# MCU.net
KiCad netlist of a schematic drawn in Altium Designer
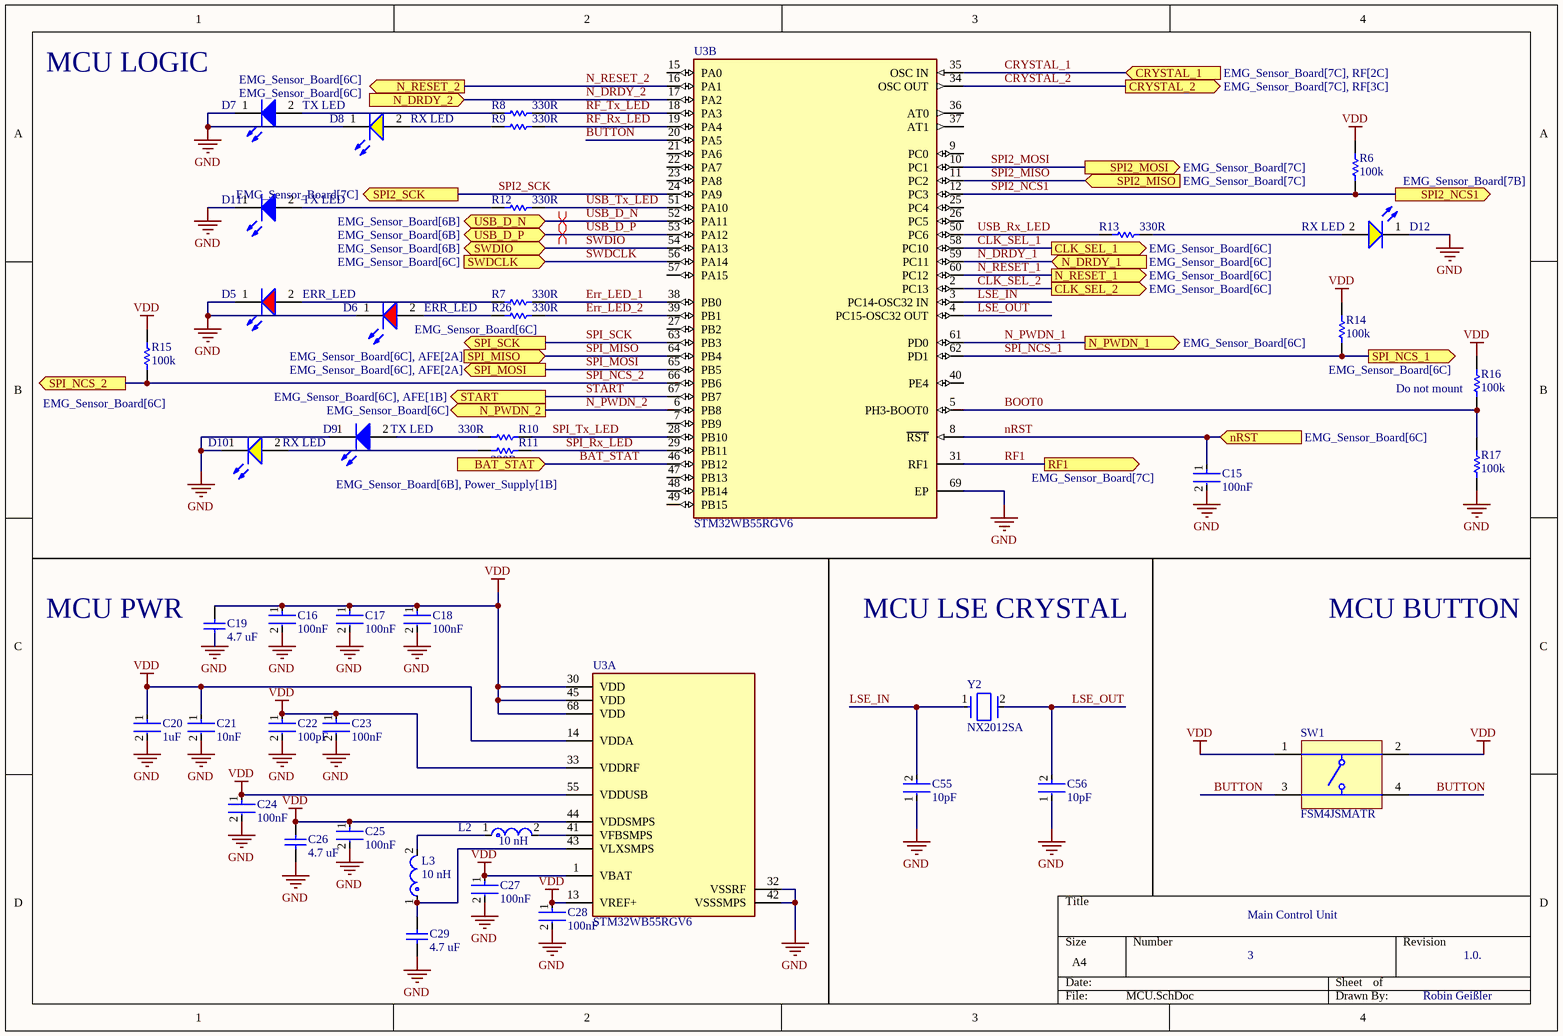
[diagram p0: MCU.SchDoc]

(export (version "E")
  (design (tool "Eeschema 10.0.6"))
  (components
    (comp (ref "C15")
      (value "100nF")
      (footprint "FP-CGA3E-0_3-0_1-IPC_A")
      (description "Cap Ceramic 100nF 50V X7R 10% Pad SMD 0603 +125°C Automotive T/R")
      (fields (field (name "TOLERANCE") "10%") (field (name "VOLTAGE") "50V"))
      (libsource (lib "Altium Content Vault") (part "b4654b650e69147ec39a6b967a45e02"))
    )
    (comp (ref "C16")
      (value "100nF")
      (footprint "FP-CGA3E-0_3-0_1-IPC_A")
      (description "Cap Ceramic 100nF 50V X7R 10% Pad SMD 0603 +125°C Automotive T/R")
      (fields (field (name "TOLERANCE") "10%") (field (name "VOLTAGE") "50V"))
      (libsource (lib "Altium Content Vault") (part "b4654b650e69147ec39a6b967a45e02"))
    )
    (comp (ref "C17")
      (value "100nF")
      (footprint "FP-CGA3E-0_3-0_1-IPC_A")
      (description "Cap Ceramic 100nF 50V X7R 10% Pad SMD 0603 +125°C Automotive T/R")
      (fields (field (name "TOLERANCE") "10%") (field (name "VOLTAGE") "50V"))
      (libsource (lib "Altium Content Vault") (part "b4654b650e69147ec39a6b967a45e02"))
    )
    (comp (ref "C18")
      (value "100nF")
      (footprint "FP-CGA3E-0_3-0_1-IPC_A")
      (description "Cap Ceramic 100nF 50V X7R 10% Pad SMD 0603 +125°C Automotive T/R")
      (fields (field (name "TOLERANCE") "10%") (field (name "VOLTAGE") "50V"))
      (libsource (lib "Altium Content Vault") (part "b4654b650e69147ec39a6b967a45e02"))
    )
    (comp (ref "C19")
      (value "4.7 uF")
      (footprint "C-1608 [0603]-N")
      (description "CAP CER 0603 16V 4.70uF X5R 10%")
      (libsource (lib "M3Infekt_V2") (part "C4u7_0603_C1608X5R1C475K080AE"))
    )
    (comp (ref "C20")
      (value "1uF")
      (footprint "FP-CGA3E-0_3-0_1-IPC_B")
      (description "Cap Ceramic 1uF 35V X7R 10% Pad SMD 0603 +125°C Automotive T/R")
      (fields (field (name "TOLERANCE") "10%"))
      (libsource (lib "Altium Content Vault") (part "b4654b650e69147ec39a6b967a45e02"))
    )
    (comp (ref "C21")
      (value "10nF")
      (footprint "FP-CC0603-DA-MFG")
      (description "CAP CER 10000PF 50V X7R 0603")
      (fields (field (name "TOLERANCE") "0.1") (field (name "MANUFACTURER PART NUMBER") "CC0603KRX7R9BB103"))
      (libsource (lib "Altium Content Vault") (part "11868f565c42a9108669ba33697ecf6"))
    )
    (comp (ref "C22")
      (value "100pF")
      (footprint "FP-C0603C-CF-MFG")
      (description "CAP CER 100PF 50V C0G/NP0 0603")
      (fields (field (name "MANUFACTURER PART NUMBER") "C0603C101J5GACTU") (field (name "TOLERANCE") "0.05"))
      (libsource (lib "Altium Content Vault") (part "b4654b650e69147ec39a6b967a45e02"))
    )
    (comp (ref "C23")
      (value "100nF")
      (footprint "FP-CGA3E-0_3-0_1-IPC_A")
      (description "Cap Ceramic 100nF 50V X7R 10% Pad SMD 0603 +125°C Automotive T/R")
      (fields (field (name "TOLERANCE") "10%") (field (name "VOLTAGE") "50V"))
      (libsource (lib "Altium Content Vault") (part "b4654b650e69147ec39a6b967a45e02"))
    )
    (comp (ref "C24")
      (value "100nF")
      (footprint "FP-CGA3E-0_3-0_1-IPC_A")
      (description "Cap Ceramic 100nF 50V X7R 10% Pad SMD 0603 +125°C Automotive T/R")
      (fields (field (name "TOLERANCE") "10%") (field (name "VOLTAGE") "50V"))
      (libsource (lib "Altium Content Vault") (part "b4654b650e69147ec39a6b967a45e02"))
    )
    (comp (ref "C25")
      (value "100nF")
      (footprint "FP-CGA3E-0_3-0_1-IPC_A")
      (description "Cap Ceramic 100nF 50V X7R 10% Pad SMD 0603 +125°C Automotive T/R")
      (fields (field (name "TOLERANCE") "10%") (field (name "VOLTAGE") "50V"))
      (libsource (lib "Altium Content Vault") (part "b4654b650e69147ec39a6b967a45e02"))
    )
    (comp (ref "C26")
      (value "4.7 uF")
      (footprint "C-1608 [0603]-N")
      (description "CAP CER 0603 16V 4.70uF X5R 10%")
      (libsource (lib "M3Infekt_V2") (part "C4u7_0603_C1608X5R1C475K080AE"))
    )
    (comp (ref "C27")
      (value "100nF")
      (footprint "FP-CGA3E-0_3-0_1-IPC_A")
      (description "Cap Ceramic 100nF 50V X7R 10% Pad SMD 0603 +125°C Automotive T/R")
      (fields (field (name "TOLERANCE") "10%") (field (name "VOLTAGE") "50V"))
      (libsource (lib "Altium Content Vault") (part "b4654b650e69147ec39a6b967a45e02"))
    )
    (comp (ref "C28")
      (value "100nF")
      (footprint "FP-CGA3E-0_3-0_1-IPC_A")
      (description "Cap Ceramic 100nF 50V X7R 10% Pad SMD 0603 +125°C Automotive T/R")
      (fields (field (name "TOLERANCE") "10%") (field (name "VOLTAGE") "50V"))
      (libsource (lib "Altium Content Vault") (part "b4654b650e69147ec39a6b967a45e02"))
    )
    (comp (ref "C29")
      (value "4.7 uF")
      (footprint "C-1608 [0603]-N")
      (description "CAP CER 0603 16V 4.70uF X5R 10%")
      (libsource (lib "M3Infekt_V2") (part "C4u7_0603_C1608X5R1C475K080AE"))
    )
    (comp (ref "C55")
      (value "10pF")
      (footprint "FP-C1608-080-0_1-IPC_C")
      (description "Multilayer Ceramic Capacitors 10pF ±0.5pF 50V C0G SMD 0603")
      (fields (field (name "VOLTAGE") "50V") (field (name "TOLERANCE") "5%"))
      (libsource (lib "Altium Content Vault") (part "236180d848d6139a670b325ea6854c9"))
    )
    (comp (ref "C56")
      (value "10pF")
      (footprint "FP-C1608-080-0_1-IPC_C")
      (description "Multilayer Ceramic Capacitors 10pF ±0.5pF 50V C0G SMD 0603")
      (fields (field (name "VOLTAGE") "50V") (field (name "TOLERANCE") "5%"))
      (libsource (lib "Altium Content Vault") (part "236180d848d6139a670b325ea6854c9"))
    )
    (comp (ref "D5")
      (value "ERR_LED")
      (footprint "WL-SMCW_0603_150060xx75000")
      (libsource (lib "Altium Content Vault") (part "LED_Red_2A-1K"))
    )
    (comp (ref "D6")
      (value "ERR_LED")
      (footprint "WL-SMCW_0603_150060xx75000")
      (libsource (lib "Altium Content Vault") (part "LED_Red_2A-1K"))
    )
    (comp (ref "D7")
      (value "TX LED")
      (footprint "WL-SMCW_0603_150060xx75000")
      (libsource (lib "Altium Content Vault") (part "LED_Blue_2A-1K"))
    )
    (comp (ref "D8")
      (value "RX LED")
      (footprint "WL-SMCW_0603_150060xx75000")
      (libsource (lib "Altium Content Vault") (part "LED_Yellow_2A-1K"))
    )
    (comp (ref "D9")
      (value "TX LED")
      (footprint "WL-SMCW_0603_150060xx75000")
      (libsource (lib "Altium Content Vault") (part "LED_Blue_2A-1K"))
    )
    (comp (ref "D10")
      (value "RX LED")
      (footprint "WL-SMCW_0603_150060xx75000")
      (libsource (lib "Altium Content Vault") (part "LED_Yellow_2A-1K"))
    )
    (comp (ref "D11")
      (value "TX LED")
      (footprint "WL-SMCW_0603_150060xx75000")
      (libsource (lib "Altium Content Vault") (part "LED_Blue_2A-1K"))
    )
    (comp (ref "D12")
      (value "RX LED")
      (footprint "WL-SMCW_0603_150060xx75000")
      (libsource (lib "Altium Content Vault") (part "LED_Yellow_2A-1K"))
    )
    (comp (ref "L2")
      (value "10 nH")
      (footprint "FP-LQG18HH_00-MFG")
      (description "Multilayer type RF Inductor 10nH ±5% 0.3Ω 650mA 0603")
      (fields (field (name "TOLERANCE") "5%"))
      (libsource (lib "Altium Content Vault") (part "4cc4b267dca4c8e51f7102f422741d8"))
    )
    (comp (ref "L3")
      (value "10 nH")
      (footprint "FP-LQG18HH_00-MFG")
      (description "Multilayer type RF Inductor 10nH ±5% 0.3Ω 650mA 0603")
      (fields (field (name "TOLERANCE") "5%"))
      (libsource (lib "Altium Content Vault") (part "4cc4b267dca4c8e51f7102f422741d8"))
    )
    (comp (ref "R6")
      (value "100k")
      (footprint "RESC1609X55X30ML10T20")
      (description "TNPW0603100KBEEA")
      (fields (field (name "MANUFACTURER") "Vishay Dale"))
      (libsource (lib "Altium Content Vault") (part "RES"))
    )
    (comp (ref "R7")
      (value "330R")
      (footprint "RESC1608X55X30LL15T15")
      (description "Chip Resistor, 330 Ohm, +/- 1%, 0.1 W, -55 to 155 degC, 0603 (1608 Metric), RoHS, Tape and Reel")
      (libsource (lib "Altium Content Vault") (part "RES-2"))
    )
    (comp (ref "R8")
      (value "330R")
      (footprint "RESC1608X55X30LL15T15")
      (description "Chip Resistor, 330 Ohm, +/- 1%, 0.1 W, -55 to 155 degC, 0603 (1608 Metric), RoHS, Tape and Reel")
      (libsource (lib "Altium Content Vault") (part "RES-2"))
    )
    (comp (ref "R9")
      (value "330R")
      (footprint "RESC1608X55X30LL15T15")
      (description "Chip Resistor, 330 Ohm, +/- 1%, 0.1 W, -55 to 155 degC, 0603 (1608 Metric), RoHS, Tape and Reel")
      (libsource (lib "Altium Content Vault") (part "RES-2"))
    )
    (comp (ref "R10")
      (value "330R")
      (footprint "RESC1608X55X30LL15T15")
      (description "Chip Resistor, 330 Ohm, +/- 1%, 0.1 W, -55 to 155 degC, 0603 (1608 Metric), RoHS, Tape and Reel")
      (libsource (lib "Altium Content Vault") (part "RES-2"))
    )
    (comp (ref "R11")
      (value "330R")
      (footprint "RESC1608X55X30LL15T15")
      (description "Chip Resistor, 330 Ohm, +/- 1%, 0.1 W, -55 to 155 degC, 0603 (1608 Metric), RoHS, Tape and Reel")
      (libsource (lib "Altium Content Vault") (part "RES-2"))
    )
    (comp (ref "R12")
      (value "330R")
      (footprint "RESC1608X55X30LL15T15")
      (description "Chip Resistor, 330 Ohm, +/- 1%, 0.1 W, -55 to 155 degC, 0603 (1608 Metric), RoHS, Tape and Reel")
      (libsource (lib "Altium Content Vault") (part "RES-2"))
    )
    (comp (ref "R13")
      (value "330R")
      (footprint "RESC1608X55X30LL15T15")
      (description "Chip Resistor, 330 Ohm, +/- 1%, 0.1 W, -55 to 155 degC, 0603 (1608 Metric), RoHS, Tape and Reel")
      (libsource (lib "Altium Content Vault") (part "RES-2"))
    )
    (comp (ref "R14")
      (value "100k")
      (footprint "RESC1609X55X30ML10T20")
      (description "TNPW0603100KBEEA")
      (fields (field (name "MANUFACTURER") "Vishay Dale"))
      (libsource (lib "Altium Content Vault") (part "RES"))
    )
    (comp (ref "R15")
      (value "100k")
      (footprint "RESC1609X55X30ML10T20")
      (description "TNPW0603100KBEEA")
      (fields (field (name "MANUFACTURER") "Vishay Dale"))
      (libsource (lib "Altium Content Vault") (part "RES"))
    )
    (comp (ref "R16")
      (value "100k")
      (footprint "RESC1609X55X30ML10T20")
      (description "TNPW0603100KBEEA")
      (fields (field (name "MANUFACTURER") "Vishay Dale"))
      (libsource (lib "Altium Content Vault") (part "RES"))
    )
    (comp (ref "R17")
      (value "100k")
      (footprint "RESC1609X55X30ML10T20")
      (description "TNPW0603100KBEEA")
      (fields (field (name "MANUFACTURER") "Vishay Dale"))
      (libsource (lib "Altium Content Vault") (part "RES"))
    )
    (comp (ref "R26")
      (value "330R")
      (footprint "RESC1608X55X30LL15T15")
      (description "Chip Resistor, 330 Ohm, +/- 1%, 0.1 W, -55 to 155 degC, 0603 (1608 Metric), RoHS, Tape and Reel")
      (libsource (lib "Altium Content Vault") (part "RES-2"))
    )
    (comp (ref "SW1")
      (value "FSM4JSMATR")
      (footprint "TECO-FSM4JSMATR_V")
      (description "Micro Miniature Push Button Switch FSM JSM, 50 mA, -35 to 85 degC, 4-Pin SMD, RoHS, Tape and Reel")
      (fields (field (name "MANUFACTURER") "TE Connectivity"))
      (libsource (lib "Altium Content Vault") (part "SW-SPST-4_A"))
    )
    (comp (ref "U3")
      (value "STM32WB55RGV6")
      (footprint "FP-VFQFPN-68-B029-MFG")
      (description "ULTRA-LOW-POWER DUAL CORE ARM CO")
      (fields
        (field (name "OCTOPART") "https://octopart.com/stm32wb55rgv6-stmicroelectronics-98750848")
        (field (name "MANUFACTURER") "STMicroelectronics")
      )
      (libsource (lib "Altium Content Vault") (part "1f6e54ba101fb6d44bf85b07b8541cc"))
    )
    (comp (ref "Y2")
      (value "NX2012SA")
      (footprint "FP-NX2012SA-MFG")
      (description "CRYSTAL 32.7680KHZ 12.5PF SMD")
      (libsource (lib "Altium Content Vault") (part "c23a69dc6c9e2f18f2079038eb95dd1"))
    )
  )
  (nets
    (net (code "1") (name "/BAT_STAT") (class "Default")
      (node (ref "U3") (pin "46") (pinfunction "PB12_46") (pintype "bidirectional"))
    )
    (net (code "2") (name "/BOOT0") (class "Default")
      (node (ref "R16") (pin "1") (pinfunction "1_1") (pintype "passive"))
      (node (ref "R17") (pin "2") (pinfunction "2_2") (pintype "passive"))
      (node (ref "U3") (pin "5") (pinfunction "PH3-BOOT0_5") (pintype "bidirectional"))
    )
    (net (code "3") (name "/BUTTON") (class "Default")
      (node (ref "SW1") (pin "3") (pinfunction "3_3") (pintype "passive"))
      (node (ref "SW1") (pin "4") (pinfunction "4_4") (pintype "passive"))
      (node (ref "U3") (pin "20") (pinfunction "PA5_20") (pintype "bidirectional"))
    )
    (net (code "4") (name "/CLK_SEL_1") (class "Default")
      (node (ref "U3") (pin "58") (pinfunction "PC10_58") (pintype "bidirectional"))
    )
    (net (code "5") (name "/CLK_SEL_2") (class "Default")
      (node (ref "U3") (pin "2") (pinfunction "PC13_2") (pintype "bidirectional"))
    )
    (net (code "6") (name "/CRYSTAL_1") (class "Default")
      (node (ref "U3") (pin "35") (pinfunction "OSC_IN_35") (pintype "input"))
    )
    (net (code "7") (name "/CRYSTAL_2") (class "Default")
      (node (ref "U3") (pin "34") (pinfunction "OSC_OUT_34") (pintype "output"))
    )
    (net (code "8") (name "/Err_LED_1") (class "Default")
      (node (ref "R7") (pin "2") (pinfunction "2_2") (pintype "passive"))
      (node (ref "U3") (pin "38") (pinfunction "PB0_38") (pintype "bidirectional"))
    )
    (net (code "9") (name "/Err_LED_2") (class "Default")
      (node (ref "R26") (pin "2") (pinfunction "2_2") (pintype "passive"))
      (node (ref "U3") (pin "39") (pinfunction "PB1_39") (pintype "bidirectional"))
    )
    (net (code "10") (name "/LSE_IN") (class "Default")
      (node (ref "C55") (pin "2") (pinfunction "2_2") (pintype "passive"))
      (node (ref "U3") (pin "3") (pinfunction "PC14-OSC32_IN_3") (pintype "bidirectional"))
      (node (ref "Y2") (pin "1") (pinfunction "1_1") (pintype "passive"))
    )
    (net (code "11") (name "/LSE_OUT") (class "Default")
      (node (ref "C56") (pin "2") (pinfunction "2_2") (pintype "passive"))
      (node (ref "U3") (pin "4") (pinfunction "PC15-OSC32_OUT_4") (pintype "bidirectional"))
      (node (ref "Y2") (pin "2") (pinfunction "2_2") (pintype "passive"))
    )
    (net (code "12") (name "/N_DRDY_1") (class "Default")
      (node (ref "U3") (pin "59") (pinfunction "PC11_59") (pintype "bidirectional"))
    )
    (net (code "13") (name "/N_DRDY_2") (class "Default")
      (node (ref "U3") (pin "17") (pinfunction "PA2_17") (pintype "bidirectional"))
    )
    (net (code "14") (name "/N_PWDN_1") (class "Default")
      (node (ref "U3") (pin "61") (pinfunction "PD0_61") (pintype "bidirectional"))
    )
    (net (code "15") (name "/N_PWDN_2") (class "Default")
      (node (ref "U3") (pin "6") (pinfunction "PB8_6") (pintype "bidirectional"))
    )
    (net (code "16") (name "/N_RESET_1") (class "Default")
      (node (ref "U3") (pin "60") (pinfunction "PC12_60") (pintype "bidirectional"))
    )
    (net (code "17") (name "/N_RESET_2") (class "Default")
      (node (ref "U3") (pin "16") (pinfunction "PA1_16") (pintype "bidirectional"))
    )
    (net (code "18") (name "/RF1") (class "Default")
      (node (ref "U3") (pin "31") (pinfunction "RF1_31") (pintype "power_in"))
    )
    (net (code "19") (name "/RF_Rx_LED") (class "Default")
      (node (ref "R9") (pin "2") (pinfunction "2_2") (pintype "passive"))
      (node (ref "U3") (pin "19") (pinfunction "PA4_19") (pintype "bidirectional"))
    )
    (net (code "20") (name "/RF_Tx_LED") (class "Default")
      (node (ref "R8") (pin "2") (pinfunction "2_2") (pintype "passive"))
      (node (ref "U3") (pin "18") (pinfunction "PA3_18") (pintype "bidirectional"))
    )
    (net (code "21") (name "/SPI2_MISO") (class "Default")
      (node (ref "U3") (pin "11") (pinfunction "PC2_11") (pintype "bidirectional"))
    )
    (net (code "22") (name "/SPI2_MOSI") (class "Default")
      (node (ref "U3") (pin "10") (pinfunction "PC1_10") (pintype "bidirectional"))
    )
    (net (code "23") (name "/SPI2_NCS1") (class "Default")
      (node (ref "R6") (pin "1") (pinfunction "1_1") (pintype "passive"))
      (node (ref "U3") (pin "12") (pinfunction "PC3_12") (pintype "bidirectional"))
    )
    (net (code "24") (name "/SPI2_SCK") (class "Default")
      (node (ref "U3") (pin "24") (pinfunction "PA9_24") (pintype "bidirectional"))
    )
    (net (code "25") (name "/SPI_MISO") (class "Default")
      (node (ref "U3") (pin "64") (pinfunction "PB4_64") (pintype "bidirectional"))
    )
    (net (code "26") (name "/SPI_MOSI") (class "Default")
      (node (ref "U3") (pin "65") (pinfunction "PB5_65") (pintype "bidirectional"))
    )
    (net (code "27") (name "/SPI_NCS_1") (class "Default")
      (node (ref "R14") (pin "1") (pinfunction "1_1") (pintype "passive"))
      (node (ref "U3") (pin "62") (pinfunction "PD1_62") (pintype "bidirectional"))
    )
    (net (code "28") (name "/SPI_NCS_2") (class "Default")
      (node (ref "R15") (pin "1") (pinfunction "1_1") (pintype "passive"))
      (node (ref "U3") (pin "66") (pinfunction "PB6_66") (pintype "bidirectional"))
    )
    (net (code "29") (name "/SPI_Rx_LED") (class "Default")
      (node (ref "R11") (pin "1") (pinfunction "1_1") (pintype "passive"))
      (node (ref "U3") (pin "29") (pinfunction "PB11_29") (pintype "bidirectional"))
    )
    (net (code "30") (name "/SPI_SCK") (class "Default")
      (node (ref "U3") (pin "63") (pinfunction "PB3_63") (pintype "bidirectional"))
    )
    (net (code "31") (name "/SPI_Tx_LED") (class "Default")
      (node (ref "R10") (pin "1") (pinfunction "1_1") (pintype "passive"))
      (node (ref "U3") (pin "28") (pinfunction "PB10_28") (pintype "bidirectional"))
    )
    (net (code "32") (name "/START") (class "Default")
      (node (ref "U3") (pin "67") (pinfunction "PB7_67") (pintype "bidirectional"))
    )
    (net (code "33") (name "/SWDCLK") (class "Default")
      (node (ref "U3") (pin "56") (pinfunction "PA14_56") (pintype "bidirectional"))
    )
    (net (code "34") (name "/SWDIO") (class "Default")
      (node (ref "U3") (pin "54") (pinfunction "PA13_54") (pintype "bidirectional"))
    )
    (net (code "35") (name "/USB_D_N") (class "Default")
      (node (ref "U3") (pin "52") (pinfunction "PA11_52") (pintype "bidirectional"))
    )
    (net (code "36") (name "/USB_D_P") (class "Default")
      (node (ref "U3") (pin "53") (pinfunction "PA12_53") (pintype "bidirectional"))
    )
    (net (code "37") (name "/USB_Rx_LED") (class "Default")
      (node (ref "R13") (pin "1") (pinfunction "1_1") (pintype "passive"))
      (node (ref "U3") (pin "50") (pinfunction "PC6_50") (pintype "bidirectional"))
    )
    (net (code "38") (name "/USB_Tx_LED") (class "Default")
      (node (ref "R12") (pin "2") (pinfunction "2_2") (pintype "passive"))
      (node (ref "U3") (pin "51") (pinfunction "PA10_51") (pintype "bidirectional"))
    )
    (net (code "39") (name "/nRST") (class "Default")
      (node (ref "C15") (pin "1") (pinfunction "1_1") (pintype "passive"))
      (node (ref "U3") (pin "8") (pinfunction "~{RST}_8") (pintype "input"))
    )
    (net (code "40") (name "GND") (class "Default")
      (node (ref "C15") (pin "2") (pinfunction "2_2") (pintype "passive"))
      (node (ref "C16") (pin "2") (pinfunction "2_2") (pintype "passive"))
      (node (ref "C17") (pin "2") (pinfunction "2_2") (pintype "passive"))
      (node (ref "C18") (pin "2") (pinfunction "2_2") (pintype "passive"))
      (node (ref "C19") (pin "1") (pinfunction "1_1") (pintype "passive"))
      (node (ref "C20") (pin "2") (pinfunction "2_2") (pintype "passive"))
      (node (ref "C21") (pin "2") (pinfunction "2_2") (pintype "passive"))
      (node (ref "C22") (pin "2") (pinfunction "2_2") (pintype "passive"))
      (node (ref "C23") (pin "2") (pinfunction "2_2") (pintype "passive"))
      (node (ref "C24") (pin "2") (pinfunction "2_2") (pintype "passive"))
      (node (ref "C25") (pin "2") (pinfunction "2_2") (pintype "passive"))
      (node (ref "C26") (pin "1") (pinfunction "1_1") (pintype "passive"))
      (node (ref "C27") (pin "2") (pinfunction "2_2") (pintype "passive"))
      (node (ref "C28") (pin "2") (pinfunction "2_2") (pintype "passive"))
      (node (ref "C29") (pin "1") (pinfunction "1_1") (pintype "passive"))
      (node (ref "C55") (pin "1") (pinfunction "1_1") (pintype "passive"))
      (node (ref "C56") (pin "1") (pinfunction "1_1") (pintype "passive"))
      (node (ref "D10") (pin "1") (pinfunction "K_1") (pintype "passive"))
      (node (ref "D11") (pin "1") (pinfunction "K_1") (pintype "passive"))
      (node (ref "D12") (pin "1") (pinfunction "K_1") (pintype "passive"))
      (node (ref "D5") (pin "1") (pinfunction "K_1") (pintype "passive"))
      (node (ref "D6") (pin "1") (pinfunction "K_1") (pintype "passive"))
      (node (ref "D7") (pin "1") (pinfunction "K_1") (pintype "passive"))
      (node (ref "D8") (pin "1") (pinfunction "K_1") (pintype "passive"))
      (node (ref "D9") (pin "1") (pinfunction "K_1") (pintype "passive"))
      (node (ref "R17") (pin "1") (pinfunction "1_1") (pintype "passive"))
      (node (ref "U3") (pin "32") (pinfunction "VSSRF_32") (pintype "power_in"))
      (node (ref "U3") (pin "42") (pinfunction "VSSSMPS_42") (pintype "power_in"))
      (node (ref "U3") (pin "69") (pinfunction "EP_69") (pintype "power_in"))
    )
    (net (code "41") (name "Net-(D5-A)") (class "Default")
      (node (ref "D5") (pin "2") (pinfunction "A_2") (pintype "passive"))
      (node (ref "R7") (pin "1") (pinfunction "1_1") (pintype "passive"))
    )
    (net (code "42") (name "Net-(D6-A)") (class "Default")
      (node (ref "D6") (pin "2") (pinfunction "A_2") (pintype "passive"))
      (node (ref "R26") (pin "1") (pinfunction "1_1") (pintype "passive"))
    )
    (net (code "43") (name "Net-(D7-A)") (class "Default")
      (node (ref "D7") (pin "2") (pinfunction "A_2") (pintype "passive"))
      (node (ref "R8") (pin "1") (pinfunction "1_1") (pintype "passive"))
    )
    (net (code "44") (name "Net-(D8-A)") (class "Default")
      (node (ref "D8") (pin "2") (pinfunction "A_2") (pintype "passive"))
      (node (ref "R9") (pin "1") (pinfunction "1_1") (pintype "passive"))
    )
    (net (code "45") (name "Net-(D9-A)") (class "Default")
      (node (ref "D9") (pin "2") (pinfunction "A_2") (pintype "passive"))
      (node (ref "R10") (pin "2") (pinfunction "2_2") (pintype "passive"))
    )
    (net (code "46") (name "Net-(D10-A)") (class "Default")
      (node (ref "D10") (pin "2") (pinfunction "A_2") (pintype "passive"))
      (node (ref "R11") (pin "2") (pinfunction "2_2") (pintype "passive"))
    )
    (net (code "47") (name "Net-(D11-A)") (class "Default")
      (node (ref "D11") (pin "2") (pinfunction "A_2") (pintype "passive"))
      (node (ref "R12") (pin "1") (pinfunction "1_1") (pintype "passive"))
    )
    (net (code "48") (name "Net-(D12-A)") (class "Default")
      (node (ref "D12") (pin "2") (pinfunction "A_2") (pintype "passive"))
      (node (ref "R13") (pin "2") (pinfunction "2_2") (pintype "passive"))
    )
    (net (code "49") (name "Net-(L2-Pad1)") (class "Default")
      (node (ref "L2") (pin "1") (pinfunction "1_1") (pintype "passive"))
      (node (ref "L3") (pin "2") (pinfunction "2_2") (pintype "passive"))
    )
    (net (code "50") (name "Net-(U3A-VFBSMPS)") (class "Default")
      (node (ref "L2") (pin "2") (pinfunction "2_2") (pintype "passive"))
      (node (ref "U3") (pin "41") (pinfunction "VFBSMPS_41") (pintype "power_in"))
    )
    (net (code "51") (name "Net-(U3A-VLXSMPS)") (class "Default")
      (node (ref "C29") (pin "2") (pinfunction "2_2") (pintype "passive"))
      (node (ref "L3") (pin "1") (pinfunction "1_1") (pintype "passive"))
      (node (ref "U3") (pin "43") (pinfunction "VLXSMPS_43") (pintype "power_in"))
    )
    (net (code "52") (name "VDD") (class "Default")
      (node (ref "C16") (pin "1") (pinfunction "1_1") (pintype "passive"))
      (node (ref "C17") (pin "1") (pinfunction "1_1") (pintype "passive"))
      (node (ref "C18") (pin "1") (pinfunction "1_1") (pintype "passive"))
      (node (ref "C19") (pin "2") (pinfunction "2_2") (pintype "passive"))
      (node (ref "C20") (pin "1") (pinfunction "1_1") (pintype "passive"))
      (node (ref "C21") (pin "1") (pinfunction "1_1") (pintype "passive"))
      (node (ref "C22") (pin "1") (pinfunction "1_1") (pintype "passive"))
      (node (ref "C23") (pin "1") (pinfunction "1_1") (pintype "passive"))
      (node (ref "C24") (pin "1") (pinfunction "1_1") (pintype "passive"))
      (node (ref "C25") (pin "1") (pinfunction "1_1") (pintype "passive"))
      (node (ref "C26") (pin "2") (pinfunction "2_2") (pintype "passive"))
      (node (ref "C27") (pin "1") (pinfunction "1_1") (pintype "passive"))
      (node (ref "C28") (pin "1") (pinfunction "1_1") (pintype "passive"))
      (node (ref "R14") (pin "2") (pinfunction "2_2") (pintype "passive"))
      (node (ref "R15") (pin "2") (pinfunction "2_2") (pintype "passive"))
      (node (ref "R16") (pin "2") (pinfunction "2_2") (pintype "passive"))
      (node (ref "R6") (pin "2") (pinfunction "2_2") (pintype "passive"))
      (node (ref "SW1") (pin "1") (pinfunction "1_1") (pintype "passive"))
      (node (ref "SW1") (pin "2") (pinfunction "2_2") (pintype "passive"))
      (node (ref "U3") (pin "1") (pinfunction "VBAT_1") (pintype "power_in"))
      (node (ref "U3") (pin "13") (pinfunction "VREF+_13") (pintype "power_in"))
      (node (ref "U3") (pin "14") (pinfunction "VDDA_14") (pintype "power_in"))
      (node (ref "U3") (pin "30") (pinfunction "VDD_30") (pintype "power_in"))
      (node (ref "U3") (pin "33") (pinfunction "VDDRF_33") (pintype "power_in"))
      (node (ref "U3") (pin "44") (pinfunction "VDDSMPS_44") (pintype "power_in"))
      (node (ref "U3") (pin "45") (pinfunction "VDD_45") (pintype "power_in"))
      (node (ref "U3") (pin "55") (pinfunction "VDDUSB_55") (pintype "power_in"))
      (node (ref "U3") (pin "68") (pinfunction "VDD_68") (pintype "power_in"))
    )
    (net (code "53") (name "unconnected-(U3B-AT0-Pad36)") (class "Default")
      (node (ref "U3") (pin "36") (pinfunction "AT0_36") (pintype "output"))
    )
    (net (code "54") (name "unconnected-(U3B-AT1-Pad37)") (class "Default")
      (node (ref "U3") (pin "37") (pinfunction "AT1_37") (pintype "output"))
    )
    (net (code "55") (name "unconnected-(U3B-PA0-Pad15)") (class "Default")
      (node (ref "U3") (pin "15") (pinfunction "PA0_15") (pintype "bidirectional"))
    )
    (net (code "56") (name "unconnected-(U3B-PA6-Pad21)") (class "Default")
      (node (ref "U3") (pin "21") (pinfunction "PA6_21") (pintype "bidirectional"))
    )
    (net (code "57") (name "unconnected-(U3B-PA7-Pad22)") (class "Default")
      (node (ref "U3") (pin "22") (pinfunction "PA7_22") (pintype "bidirectional"))
    )
    (net (code "58") (name "unconnected-(U3B-PA8-Pad23)") (class "Default")
      (node (ref "U3") (pin "23") (pinfunction "PA8_23") (pintype "bidirectional"))
    )
    (net (code "59") (name "unconnected-(U3B-PA15-Pad57)") (class "Default")
      (node (ref "U3") (pin "57") (pinfunction "PA15_57") (pintype "bidirectional"))
    )
    (net (code "60") (name "unconnected-(U3B-PB2-Pad27)") (class "Default")
      (node (ref "U3") (pin "27") (pinfunction "PB2_27") (pintype "bidirectional"))
    )
    (net (code "61") (name "unconnected-(U3B-PB9-Pad7)") (class "Default")
      (node (ref "U3") (pin "7") (pinfunction "PB9_7") (pintype "bidirectional"))
    )
    (net (code "62") (name "unconnected-(U3B-PB13-Pad47)") (class "Default")
      (node (ref "U3") (pin "47") (pinfunction "PB13_47") (pintype "bidirectional"))
    )
    (net (code "63") (name "unconnected-(U3B-PB14-Pad48)") (class "Default")
      (node (ref "U3") (pin "48") (pinfunction "PB14_48") (pintype "bidirectional"))
    )
    (net (code "64") (name "unconnected-(U3B-PB15-Pad49)") (class "Default")
      (node (ref "U3") (pin "49") (pinfunction "PB15_49") (pintype "bidirectional"))
    )
    (net (code "65") (name "unconnected-(U3B-PC0-Pad9)") (class "Default")
      (node (ref "U3") (pin "9") (pinfunction "PC0_9") (pintype "bidirectional"))
    )
    (net (code "66") (name "unconnected-(U3B-PC4-Pad25)") (class "Default")
      (node (ref "U3") (pin "25") (pinfunction "PC4_25") (pintype "bidirectional"))
    )
    (net (code "67") (name "unconnected-(U3B-PC5-Pad26)") (class "Default")
      (node (ref "U3") (pin "26") (pinfunction "PC5_26") (pintype "bidirectional"))
    )
    (net (code "68") (name "unconnected-(U3B-PE4-Pad40)") (class "Default")
      (node (ref "U3") (pin "40") (pinfunction "PE4_40") (pintype "bidirectional"))
    )
  )
)
